# RGB_sensor.net
KiCad netlist of a schematic drawn in Altium Designer
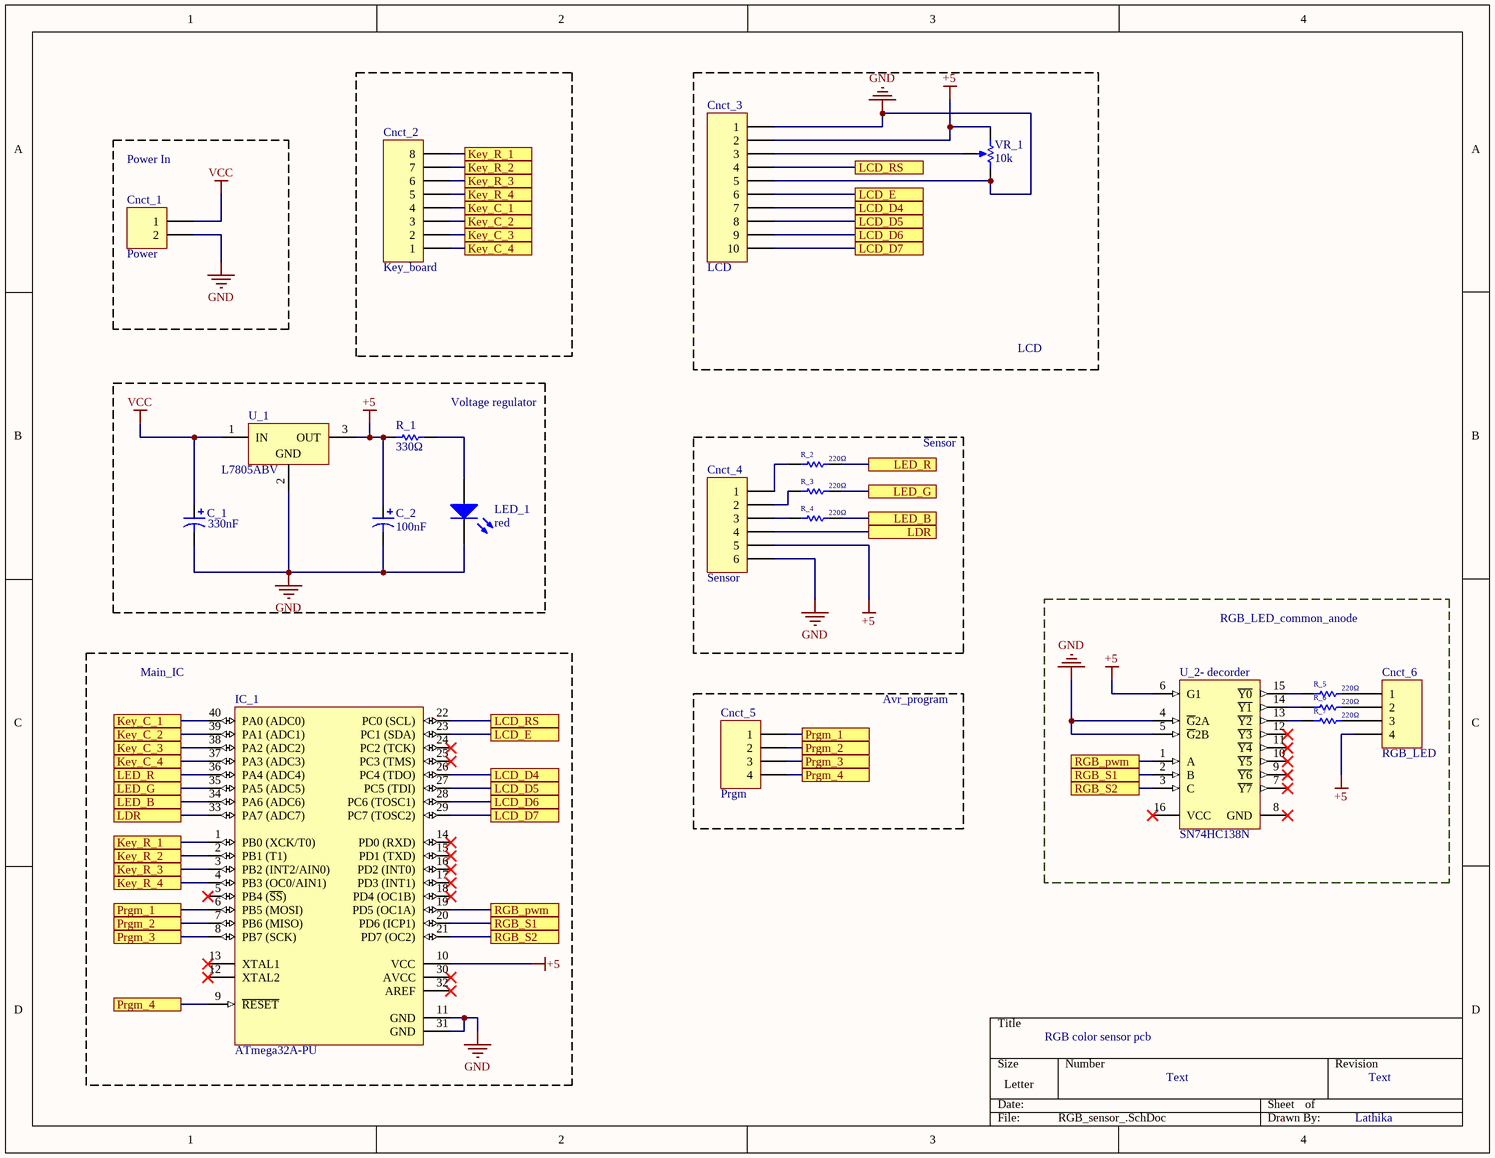
[diagram p0: RGB_sensor_.SchDoc]

(export (version "E")
  (design (tool "Eeschema 10.0.6"))
  (components
    (comp (ref "Cnct_1")
      (value "Power")
      (footprint "HDR1X2")
      (description "Header, 2-Pin")
      (fields (field (name "PUBLISHER") "Altium Limited"))
      (libsource (lib "Miscellaneous Connectors") (part "Header 2"))
    )
    (comp (ref "Cnct_2")
      (value "Key_board")
      (footprint "HDR1X8")
      (description "Header, 8-Pin")
      (fields (field (name "PUBLISHER") "Altium Limited"))
      (libsource (lib "Miscellaneous Connectors") (part "Header 8"))
    )
    (comp (ref "Cnct_3")
      (value "LCD")
      (footprint "HDR1X10")
      (description "Header, 10-Pin")
      (fields (field (name "PUBLISHER") "Altium Limited"))
      (libsource (lib "Miscellaneous Connectors") (part "Header 10"))
    )
    (comp (ref "Cnct_4")
      (value "Sensor")
      (footprint "HDR1X6")
      (description "Header, 6-Pin")
      (fields (field (name "PUBLISHER") "Altium Limited"))
      (libsource (lib "Miscellaneous Connectors") (part "Header 6"))
    )
    (comp (ref "Cnct_5")
      (value "Prgm")
      (footprint "HDR1X4")
      (description "Header, 4-Pin")
      (fields (field (name "PUBLISHER") "Altium Limited"))
      (libsource (lib "Miscellaneous Connectors") (part "Header 4"))
    )
    (comp (ref "Cnct_6")
      (value "RGB_LED")
      (footprint "HDR1X4")
      (description "Header, 4-Pin")
      (fields (field (name "PUBLISHER") "Altium Limited"))
      (libsource (lib "") (part "Header 4_1"))
    )
    (comp (ref "C_1")
      (value "330nF")
      (footprint "RB7.6-15")
      (description "Polarized Capacitor (Radial)")
      (fields (field (name "PUBLISHER") "Altium Limited"))
      (libsource (lib "Miscellaneous Devices") (part "Cap Pol1"))
    )
    (comp (ref "C_2")
      (value "100nF")
      (footprint "RB7.6-15")
      (description "Polarized Capacitor (Radial)")
      (fields (field (name "PUBLISHER") "Altium Limited"))
      (libsource (lib "Miscellaneous Devices") (part "Cap Pol1"))
    )
    (comp (ref "IC_1")
      (value "ATmega32A-PU")
      (footprint "40P6")
      (libsource (lib "Altium Content Vault") (part "MC-8B-AT16A-IL40"))
    )
    (comp (ref "LED_1")
      (value "red")
      (footprint "Type 5mm")
      (description "THT LED round mono-color color lens, WL-TMRW, Red")
      (fields (field (name "PARTNUMBER") "151051RS11000") (field (name "MANUFACTURER") "Wuerth Elektronik"))
      (libsource (lib "Altium Content Vault") (part "WE-LED_K1A2-2"))
    )
    (comp (ref "R_1")
      (value "330Ω")
      (footprint "AXIAL-0.3")
      (description "Resistor")
      (fields (field (name "PUBLISHER") "Altium Limited"))
      (libsource (lib "Miscellaneous Devices") (part "Res1"))
    )
    (comp (ref "R_2")
      (value "220Ω")
      (footprint "AXIAL-0.3")
      (description "Resistor")
      (fields (field (name "PUBLISHER") "Altium Limited"))
      (libsource (lib "Miscellaneous Devices") (part "Res1"))
    )
    (comp (ref "R_3")
      (value "220Ω")
      (footprint "AXIAL-0.3")
      (description "Resistor")
      (fields (field (name "PUBLISHER") "Altium Limited"))
      (libsource (lib "Miscellaneous Devices") (part "Res1"))
    )
    (comp (ref "R_4")
      (value "220Ω")
      (footprint "AXIAL-0.3")
      (description "Resistor")
      (fields (field (name "PUBLISHER") "Altium Limited"))
      (libsource (lib "Miscellaneous Devices") (part "Res1"))
    )
    (comp (ref "R_5")
      (value "220Ω")
      (footprint "AXIAL-0.3")
      (description "Resistor")
      (fields (field (name "PUBLISHER") "Altium Limited"))
      (libsource (lib "Miscellaneous Devices") (part "Res1"))
    )
    (comp (ref "R_6")
      (value "220Ω")
      (footprint "AXIAL-0.3")
      (description "Resistor")
      (fields (field (name "PUBLISHER") "Altium Limited"))
      (libsource (lib "Miscellaneous Devices") (part "Res1"))
    )
    (comp (ref "R_7")
      (value "220Ω")
      (footprint "AXIAL-0.3")
      (description "Resistor")
      (fields (field (name "PUBLISHER") "Altium Limited"))
      (libsource (lib "Miscellaneous Devices") (part "Res1"))
    )
    (comp (ref "U_1")
      (value "L7805ABV")
      (footprint "TO220")
      (description "Positive Voltage Regulator, 5V, 3-Pin TO-220")
      (libsource (lib "Altium Content Vault") (part "PM-REG-L4940-SIL3"))
    )
    (comp (ref "U_2- decorder")
      (value "SN74HC138N")
      (footprint "N0016A")
      (description "3-Line To 8-Line Decoders/Demultiplexers, N0016A, TUBE")
      (fields
        (field (name "MANUFACTURER") "Texas Instruments")
        (field (name "GENERIC PART NUMBER") "SN74HC138")
      )
      (libsource (lib "Altium Content Vault") (part "TI-SNX4XXXX138-16"))
    )
    (comp (ref "VR_1")
      (value "10k")
      (footprint "BOUR-3362P")
      (description "Square Trimpot(R) Trimming Potentiometer, 100 KOhm, 300 V, -55 to 125 degC, 3-Pin THD, RoHS, Tube")
      (fields (field (name "TOLERANCE") "1%"))
      (libsource (lib "Altium Content Vault") (part "RES-POT-3"))
    )
  )
  (nets
    (net (code "1") (name "+5") (class "Default")
      (node (ref "C_2") (pin "1") (pinfunction "1_1") (pintype "passive"))
      (node (ref "Cnct_3") (pin "2") (pinfunction "2_2") (pintype "passive"))
      (node (ref "Cnct_4") (pin "5") (pinfunction "5_5") (pintype "passive"))
      (node (ref "Cnct_6") (pin "4") (pinfunction "4_4") (pintype "passive"))
      (node (ref "IC_1") (pin "10") (pinfunction "VCC_10") (pintype "power_in"))
      (node (ref "R_1") (pin "1") (pinfunction "1_1") (pintype "passive"))
      (node (ref "U_1") (pin "3") (pinfunction "OUT_3") (pintype "power_in"))
      (node (ref "U_2- decorder") (pin "6") (pinfunction "G1_6") (pintype "input"))
      (node (ref "VR_1") (pin "1") (pinfunction "CCW_1") (pintype "passive"))
    )
    (net (code "2") (name "/Key_C_1") (class "Default")
      (node (ref "Cnct_2") (pin "4") (pinfunction "4_4") (pintype "passive"))
      (node (ref "IC_1") (pin "40") (pinfunction "PA0_(ADC0)_40") (pintype "bidirectional"))
    )
    (net (code "3") (name "/Key_C_2") (class "Default")
      (node (ref "Cnct_2") (pin "3") (pinfunction "3_3") (pintype "passive"))
      (node (ref "IC_1") (pin "39") (pinfunction "PA1_(ADC1)_39") (pintype "bidirectional"))
    )
    (net (code "4") (name "/Key_C_3") (class "Default")
      (node (ref "Cnct_2") (pin "2") (pinfunction "2_2") (pintype "passive"))
      (node (ref "IC_1") (pin "38") (pinfunction "PA2_(ADC2)_38") (pintype "bidirectional"))
    )
    (net (code "5") (name "/Key_C_4") (class "Default")
      (node (ref "Cnct_2") (pin "1") (pinfunction "1_1") (pintype "passive"))
      (node (ref "IC_1") (pin "37") (pinfunction "PA3_(ADC3)_37") (pintype "bidirectional"))
    )
    (net (code "6") (name "/Key_R_1") (class "Default")
      (node (ref "Cnct_2") (pin "8") (pinfunction "8_8") (pintype "passive"))
      (node (ref "IC_1") (pin "1") (pinfunction "PB0_(XCK/T0)_1") (pintype "bidirectional"))
    )
    (net (code "7") (name "/Key_R_2") (class "Default")
      (node (ref "Cnct_2") (pin "7") (pinfunction "7_7") (pintype "passive"))
      (node (ref "IC_1") (pin "2") (pinfunction "PB1_(T1)_2") (pintype "bidirectional"))
    )
    (net (code "8") (name "/Key_R_3") (class "Default")
      (node (ref "Cnct_2") (pin "6") (pinfunction "6_6") (pintype "passive"))
      (node (ref "IC_1") (pin "3") (pinfunction "PB2_(INT2/AIN0)_3") (pintype "bidirectional"))
    )
    (net (code "9") (name "/Key_R_4") (class "Default")
      (node (ref "Cnct_2") (pin "5") (pinfunction "5_5") (pintype "passive"))
      (node (ref "IC_1") (pin "4") (pinfunction "PB3_(OC0/AIN1)_4") (pintype "bidirectional"))
    )
    (net (code "10") (name "/LCD_D4") (class "Default")
      (node (ref "Cnct_3") (pin "7") (pinfunction "7_7") (pintype "passive"))
      (node (ref "IC_1") (pin "26") (pinfunction "PC4_(TDO)_26") (pintype "bidirectional"))
    )
    (net (code "11") (name "/LCD_D5") (class "Default")
      (node (ref "Cnct_3") (pin "8") (pinfunction "8_8") (pintype "passive"))
      (node (ref "IC_1") (pin "27") (pinfunction "PC5_(TDI)_27") (pintype "bidirectional"))
    )
    (net (code "12") (name "/LCD_D6") (class "Default")
      (node (ref "Cnct_3") (pin "9") (pinfunction "9_9") (pintype "passive"))
      (node (ref "IC_1") (pin "28") (pinfunction "PC6_(TOSC1)_28") (pintype "bidirectional"))
    )
    (net (code "13") (name "/LCD_D7") (class "Default")
      (node (ref "Cnct_3") (pin "10") (pinfunction "10_10") (pintype "passive"))
      (node (ref "IC_1") (pin "29") (pinfunction "PC7_(TOSC2)_29") (pintype "bidirectional"))
    )
    (net (code "14") (name "/LCD_E") (class "Default")
      (node (ref "Cnct_3") (pin "6") (pinfunction "6_6") (pintype "passive"))
      (node (ref "IC_1") (pin "23") (pinfunction "PC1_(SDA)_23") (pintype "bidirectional"))
    )
    (net (code "15") (name "/LCD_RS") (class "Default")
      (node (ref "Cnct_3") (pin "4") (pinfunction "4_4") (pintype "passive"))
      (node (ref "IC_1") (pin "22") (pinfunction "PC0_(SCL)_22") (pintype "bidirectional"))
    )
    (net (code "16") (name "/LDR") (class "Default")
      (node (ref "Cnct_4") (pin "4") (pinfunction "4_4") (pintype "passive"))
      (node (ref "IC_1") (pin "33") (pinfunction "PA7_(ADC7)_33") (pintype "bidirectional"))
    )
    (net (code "17") (name "/LED_B") (class "Default")
      (node (ref "IC_1") (pin "34") (pinfunction "PA6_(ADC6)_34") (pintype "bidirectional"))
      (node (ref "R_4") (pin "2") (pinfunction "2_2") (pintype "passive"))
    )
    (net (code "18") (name "/LED_G") (class "Default")
      (node (ref "IC_1") (pin "35") (pinfunction "PA5_(ADC5)_35") (pintype "bidirectional"))
      (node (ref "R_3") (pin "2") (pinfunction "2_2") (pintype "passive"))
    )
    (net (code "19") (name "/LED_R") (class "Default")
      (node (ref "IC_1") (pin "36") (pinfunction "PA4_(ADC4)_36") (pintype "bidirectional"))
      (node (ref "R_2") (pin "2") (pinfunction "2_2") (pintype "passive"))
    )
    (net (code "20") (name "/Prgm_1") (class "Default")
      (node (ref "Cnct_5") (pin "1") (pinfunction "1_1") (pintype "passive"))
      (node (ref "IC_1") (pin "6") (pinfunction "PB5_(MOSI)_6") (pintype "bidirectional"))
    )
    (net (code "21") (name "/Prgm_2") (class "Default")
      (node (ref "Cnct_5") (pin "2") (pinfunction "2_2") (pintype "passive"))
      (node (ref "IC_1") (pin "7") (pinfunction "PB6_(MISO)_7") (pintype "bidirectional"))
    )
    (net (code "22") (name "/Prgm_3") (class "Default")
      (node (ref "Cnct_5") (pin "3") (pinfunction "3_3") (pintype "passive"))
      (node (ref "IC_1") (pin "8") (pinfunction "PB7_(SCK)_8") (pintype "bidirectional"))
    )
    (net (code "23") (name "/Prgm_4") (class "Default")
      (node (ref "Cnct_5") (pin "4") (pinfunction "4_4") (pintype "passive"))
      (node (ref "IC_1") (pin "9") (pinfunction "~{RESET}_9") (pintype "input"))
    )
    (net (code "24") (name "/RGB_S1") (class "Default")
      (node (ref "IC_1") (pin "20") (pinfunction "PD6_(ICP1)_20") (pintype "bidirectional"))
      (node (ref "U_2- decorder") (pin "2") (pinfunction "B_2") (pintype "input"))
    )
    (net (code "25") (name "/RGB_S2") (class "Default")
      (node (ref "IC_1") (pin "21") (pinfunction "PD7_(OC2)_21") (pintype "bidirectional"))
      (node (ref "U_2- decorder") (pin "3") (pinfunction "C_3") (pintype "input"))
    )
    (net (code "26") (name "/RGB_pwm") (class "Default")
      (node (ref "IC_1") (pin "19") (pinfunction "PD5_(OC1A)_19") (pintype "bidirectional"))
      (node (ref "U_2- decorder") (pin "1") (pinfunction "A_1") (pintype "input"))
    )
    (net (code "27") (name "GND") (class "Default")
      (node (ref "C_1") (pin "2") (pinfunction "2_2") (pintype "passive"))
      (node (ref "C_2") (pin "2") (pinfunction "2_2") (pintype "passive"))
      (node (ref "Cnct_1") (pin "2") (pinfunction "2_2") (pintype "passive"))
      (node (ref "Cnct_3") (pin "1") (pinfunction "1_1") (pintype "passive"))
      (node (ref "Cnct_3") (pin "5") (pinfunction "5_5") (pintype "passive"))
      (node (ref "Cnct_4") (pin "6") (pinfunction "6_6") (pintype "passive"))
      (node (ref "IC_1") (pin "11") (pinfunction "GND_11") (pintype "power_in"))
      (node (ref "IC_1") (pin "31") (pinfunction "GND_31") (pintype "power_in"))
      (node (ref "LED_1") (pin "1") (pinfunction "K_1") (pintype "passive"))
      (node (ref "U_1") (pin "2") (pinfunction "GND_2") (pintype "power_in"))
      (node (ref "U_2- decorder") (pin "4") (pinfunction "~{G}2A_4") (pintype "input"))
      (node (ref "U_2- decorder") (pin "5") (pinfunction "~{G}2B_5") (pintype "input"))
      (node (ref "VR_1") (pin "3") (pinfunction "CW_3") (pintype "passive"))
    )
    (net (code "28") (name "Net-(Cnct_4-Pad1)") (class "Default")
      (node (ref "Cnct_4") (pin "1") (pinfunction "1_1") (pintype "passive"))
      (node (ref "R_2") (pin "1") (pinfunction "1_1") (pintype "passive"))
    )
    (net (code "29") (name "Net-(Cnct_4-Pad2)") (class "Default")
      (node (ref "Cnct_4") (pin "2") (pinfunction "2_2") (pintype "passive"))
      (node (ref "R_3") (pin "1") (pinfunction "1_1") (pintype "passive"))
    )
    (net (code "30") (name "Net-(Cnct_4-Pad3)") (class "Default")
      (node (ref "Cnct_4") (pin "3") (pinfunction "3_3") (pintype "passive"))
      (node (ref "R_4") (pin "1") (pinfunction "1_1") (pintype "passive"))
    )
    (net (code "31") (name "Net-(Cnct_6-Pad1)") (class "Default")
      (node (ref "Cnct_6") (pin "1") (pinfunction "1_1") (pintype "passive"))
      (node (ref "R_5") (pin "2") (pinfunction "2_2") (pintype "passive"))
    )
    (net (code "32") (name "Net-(Cnct_6-Pad2)") (class "Default")
      (node (ref "Cnct_6") (pin "2") (pinfunction "2_2") (pintype "passive"))
      (node (ref "R_6") (pin "2") (pinfunction "2_2") (pintype "passive"))
    )
    (net (code "33") (name "Net-(Cnct_6-Pad3)") (class "Default")
      (node (ref "Cnct_6") (pin "3") (pinfunction "3_3") (pintype "passive"))
      (node (ref "R_7") (pin "2") (pinfunction "2_2") (pintype "passive"))
    )
    (net (code "34") (name "Net-(LED_1-A)") (class "Default")
      (node (ref "LED_1") (pin "2") (pinfunction "A_2") (pintype "passive"))
      (node (ref "R_1") (pin "2") (pinfunction "2_2") (pintype "passive"))
    )
    (net (code "35") (name "Net-(U_2- decorder-~{Y0})") (class "Default")
      (node (ref "R_5") (pin "1") (pinfunction "1_1") (pintype "passive"))
      (node (ref "U_2- decorder") (pin "15") (pinfunction "~{Y0}_15") (pintype "output"))
    )
    (net (code "36") (name "Net-(U_2- decorder-~{Y1})") (class "Default")
      (node (ref "R_6") (pin "1") (pinfunction "1_1") (pintype "passive"))
      (node (ref "U_2- decorder") (pin "14") (pinfunction "~{Y1}_14") (pintype "output"))
    )
    (net (code "37") (name "Net-(U_2- decorder-~{Y2})") (class "Default")
      (node (ref "R_7") (pin "1") (pinfunction "1_1") (pintype "passive"))
      (node (ref "U_2- decorder") (pin "13") (pinfunction "~{Y2}_13") (pintype "output"))
    )
    (net (code "38") (name "Net-(VR_1-S)") (class "Default")
      (node (ref "Cnct_3") (pin "3") (pinfunction "3_3") (pintype "passive"))
      (node (ref "VR_1") (pin "2") (pinfunction "S_2") (pintype "passive"))
    )
    (net (code "39") (name "VCC") (class "Default")
      (node (ref "C_1") (pin "1") (pinfunction "1_1") (pintype "passive"))
      (node (ref "Cnct_1") (pin "1") (pinfunction "1_1") (pintype "passive"))
      (node (ref "U_1") (pin "1") (pinfunction "IN_1") (pintype "power_in"))
    )
    (net (code "40") (name "unconnected-(IC_1-AREF-Pad32)") (class "Default")
      (node (ref "IC_1") (pin "32") (pinfunction "AREF_32") (pintype "power_in+no_connect"))
    )
    (net (code "41") (name "unconnected-(IC_1-AVCC-Pad30)") (class "Default")
      (node (ref "IC_1") (pin "30") (pinfunction "AVCC_30") (pintype "power_in+no_connect"))
    )
    (net (code "42") (name "unconnected-(IC_1-PB4_(~{SS})-Pad5)") (class "Default")
      (node (ref "IC_1") (pin "5") (pinfunction "PB4_(~{SS})_5") (pintype "bidirectional+no_connect"))
    )
    (net (code "43") (name "unconnected-(IC_1-PC2_(TCK)-Pad24)") (class "Default")
      (node (ref "IC_1") (pin "24") (pinfunction "PC2_(TCK)_24") (pintype "bidirectional+no_connect"))
    )
    (net (code "44") (name "unconnected-(IC_1-PC3_(TMS)-Pad25)") (class "Default")
      (node (ref "IC_1") (pin "25") (pinfunction "PC3_(TMS)_25") (pintype "bidirectional+no_connect"))
    )
    (net (code "45") (name "unconnected-(IC_1-PD0_(RXD)-Pad14)") (class "Default")
      (node (ref "IC_1") (pin "14") (pinfunction "PD0_(RXD)_14") (pintype "bidirectional+no_connect"))
    )
    (net (code "46") (name "unconnected-(IC_1-PD1_(TXD)-Pad15)") (class "Default")
      (node (ref "IC_1") (pin "15") (pinfunction "PD1_(TXD)_15") (pintype "bidirectional+no_connect"))
    )
    (net (code "47") (name "unconnected-(IC_1-PD2_(INT0)-Pad16)") (class "Default")
      (node (ref "IC_1") (pin "16") (pinfunction "PD2_(INT0)_16") (pintype "bidirectional+no_connect"))
    )
    (net (code "48") (name "unconnected-(IC_1-PD3_(INT1)-Pad17)") (class "Default")
      (node (ref "IC_1") (pin "17") (pinfunction "PD3_(INT1)_17") (pintype "bidirectional+no_connect"))
    )
    (net (code "49") (name "unconnected-(IC_1-PD4_(OC1B)-Pad18)") (class "Default")
      (node (ref "IC_1") (pin "18") (pinfunction "PD4_(OC1B)_18") (pintype "bidirectional+no_connect"))
    )
    (net (code "50") (name "unconnected-(IC_1-XTAL1-Pad13)") (class "Default")
      (node (ref "IC_1") (pin "13") (pinfunction "XTAL1_13") (pintype "passive+no_connect"))
    )
    (net (code "51") (name "unconnected-(IC_1-XTAL2-Pad12)") (class "Default")
      (node (ref "IC_1") (pin "12") (pinfunction "XTAL2_12") (pintype "passive+no_connect"))
    )
    (net (code "52") (name "unconnected-(U_2- decorder-GND-Pad8)") (class "Default")
      (node (ref "U_2- decorder") (pin "8") (pinfunction "GND_8") (pintype "power_in+no_connect"))
    )
    (net (code "53") (name "unconnected-(U_2- decorder-VCC-Pad16)") (class "Default")
      (node (ref "U_2- decorder") (pin "16") (pinfunction "VCC_16") (pintype "power_in+no_connect"))
    )
    (net (code "54") (name "unconnected-(U_2- decorder-~{Y3}-Pad12)") (class "Default")
      (node (ref "U_2- decorder") (pin "12") (pinfunction "~{Y3}_12") (pintype "output+no_connect"))
    )
    (net (code "55") (name "unconnected-(U_2- decorder-~{Y4}-Pad11)") (class "Default")
      (node (ref "U_2- decorder") (pin "11") (pinfunction "~{Y4}_11") (pintype "output+no_connect"))
    )
    (net (code "56") (name "unconnected-(U_2- decorder-~{Y5}-Pad10)") (class "Default")
      (node (ref "U_2- decorder") (pin "10") (pinfunction "~{Y5}_10") (pintype "output+no_connect"))
    )
    (net (code "57") (name "unconnected-(U_2- decorder-~{Y6}-Pad9)") (class "Default")
      (node (ref "U_2- decorder") (pin "9") (pinfunction "~{Y6}_9") (pintype "output+no_connect"))
    )
    (net (code "58") (name "unconnected-(U_2- decorder-~{Y7}-Pad7)") (class "Default")
      (node (ref "U_2- decorder") (pin "7") (pinfunction "~{Y7}_7") (pintype "output+no_connect"))
    )
  )
)
